# 1_Main_copy.net
KiCad netlist of a schematic drawn in Altium Designer
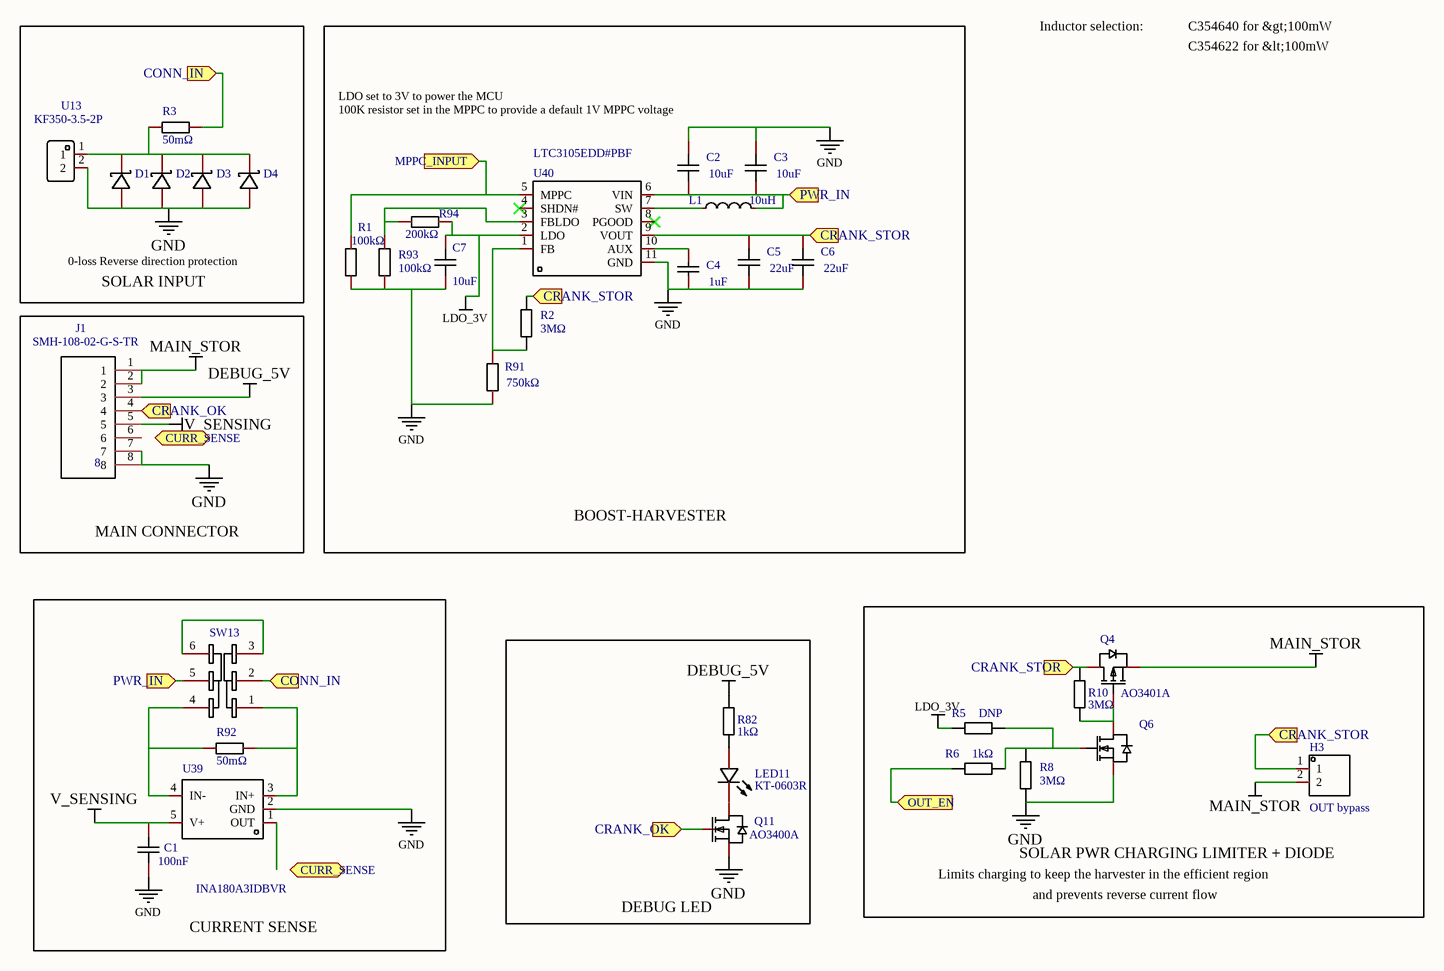
[diagram p0: 1_Main copy.schdoc]

(export (version "E")
  (design (tool "Eeschema 10.0.6"))
  (components
    (comp (ref "C1")
      (value "100nF")
      (fields
        (field (name "NAME") "100nF")
        (field (name "MANUFACTURER") "YAGEO")
        (field (name "MANUFACTURER PART") "CC0603KRX7R9BB104")
      )
      (libsource (lib "altium-import") (part "root_1_CC0603KRX7R9BB104_"))
    )
    (comp (ref "C2")
      (value "10uF")
      (fields
        (field (name "MANUFACTURER") "SAMSUNG(三星)")
        (field (name "MANUFACTURER PART") "CL10A106MA8NRNC")
        (field (name "TOLERANCE") "±20%")
      )
      (libsource (lib "altium-import") (part "root_1_CL10A106MA8NRNC_"))
    )
    (comp (ref "C3")
      (value "10uF")
      (fields
        (field (name "MANUFACTURER") "SAMSUNG(三星)")
        (field (name "MANUFACTURER PART") "CL10A106MA8NRNC")
        (field (name "TOLERANCE") "±20%")
      )
      (libsource (lib "altium-import") (part "root_1_CL10A106MA8NRNC_"))
    )
    (comp (ref "C4")
      (value "1uF")
      (fields
        (field (name "MANUFACTURER") "SAMSUNG(三星)")
        (field (name "MANUFACTURER PART") "CL10A105KB8NNNC")
        (field (name "TOLERANCE") "±10%")
      )
      (libsource (lib "altium-import") (part "root_1_CL10A105KB8NNNC_"))
    )
    (comp (ref "C5")
      (value "22uF")
      (fields
        (field (name "MANUFACTURER") "SAMSUNG(三星)")
        (field (name "MANUFACTURER PART") "CL21A226MAQNNNE")
        (field (name "TOLERANCE") "±20%")
      )
      (libsource (lib "altium-import") (part "root_1_CL21A226MAQNNNE_C45783_"))
    )
    (comp (ref "C6")
      (value "22uF")
      (fields
        (field (name "MANUFACTURER") "SAMSUNG(三星)")
        (field (name "MANUFACTURER PART") "CL21A226MAQNNNE")
        (field (name "TOLERANCE") "±20%")
      )
      (libsource (lib "altium-import") (part "root_1_CL21A226MAQNNNE_C45783_"))
    )
    (comp (ref "C7")
      (value "10uF")
      (fields
        (field (name "MANUFACTURER") "SAMSUNG(三星)")
        (field (name "MANUFACTURER PART") "CL10A106MA8NRNC")
        (field (name "TOLERANCE") "±20%")
      )
      (libsource (lib "altium-import") (part "root_1_CL10A106MA8NRNC_"))
    )
    (comp (ref "D1")
      (value "SS54")
      (description "Reverse Voltage (Vr):40V Average Rectified Current (Io):5A Forward Voltage (Vf@If):550mV@5A")
      (fields (field (name "MANUFACTURER") "MDD"))
      (libsource (lib "altium-import") (part "root_3_SS54_"))
    )
    (comp (ref "D2")
      (value "SS54")
      (description "Reverse Voltage (Vr):40V Average Rectified Current (Io):5A Forward Voltage (Vf@If):550mV@5A")
      (fields (field (name "MANUFACTURER") "MDD"))
      (libsource (lib "altium-import") (part "root_3_SS54_"))
    )
    (comp (ref "D3")
      (value "SS54")
      (description "Reverse Voltage (Vr):40V Average Rectified Current (Io):5A Forward Voltage (Vf@If):550mV@5A")
      (fields (field (name "MANUFACTURER") "MDD"))
      (libsource (lib "altium-import") (part "root_3_SS54_"))
    )
    (comp (ref "D4")
      (value "SS54")
      (description "Reverse Voltage (Vr):40V Average Rectified Current (Io):5A Forward Voltage (Vf@If):550mV@5A")
      (fields (field (name "MANUFACTURER") "MDD"))
      (libsource (lib "altium-import") (part "root_3_SS54_"))
    )
    (comp (ref "H3")
      (value "OUT bypass")
      (fields (field (name "NAME") "OUT bypass"))
      (libsource (lib "altium-import") (part "root_0_HDR-M_2.54_1x2P_"))
    )
    (comp (ref "J1")
      (value "SMH-108-02-G-S-TR")
      (fields (field (name "NAME") "SMH-108-02-G-S-TR") (field (name "NAME_1") "8"))
      (libsource (lib "altium-import") (part "root_0_SMH-108-02-G-S-TR_"))
    )
    (comp (ref "L1")
      (value "10uH")
      (fields (field (name "MANUFACTURER") "CENKER(岑科)") (field (name "MANUFACTURER PART") "CKCS6028-10uH/M"))
      (libsource (lib "altium-import") (part "root_0_CKCS6028-10uH/M_"))
    )
    (comp (ref "LED11")
      (value "KT-0603R")
      (fields (field (name "NAME") "KT-0603R") (field (name "MANUFACTURER") "KENTO"))
      (libsource (lib "altium-import") (part "root_1_KT-0603R_"))
    )
    (comp (ref "Q4")
      (value "AO3401A")
      (fields (field (name "NAME") "AO3401A") (field (name "MANUFACTURER") "AOS"))
      (libsource (lib "altium-import") (part "root_1_mirrored_AO3401A_"))
    )
    (comp (ref "Q6")
      (value "SI2302")
      (fields (field (name "MANUFACTURER") "YONGYUTAI(永裕泰)"))
      (libsource (lib "altium-import") (part "root_0_SI2302_"))
    )
    (comp (ref "Q11")
      (value "AO3400A")
      (fields (field (name "NAME") "AO3400A") (field (name "MANUFACTURER") "HUASHUO(华朔)"))
      (libsource (lib "altium-import") (part "root_0_AO3400A_"))
    )
    (comp (ref "R1")
      (value "100kΩ")
      (fields
        (field (name "MANUFACTURER") "UNI-ROYAL(厚声)")
        (field (name "MANUFACTURER PART") "0603WAF1003T5E")
        (field (name "TOLERANCE") "±1%")
      )
      (libsource (lib "altium-import") (part "root_1_0603WAF1003T5E_"))
    )
    (comp (ref "R2")
      (value "3MΩ")
      (fields
        (field (name "NAME") "3MΩ")
        (field (name "MANUFACTURER") "UniOhm")
        (field (name "MANUFACTURER PART") "0603WAF3004T5E")
      )
      (libsource (lib "altium-import") (part "root_3_0603WAF3004T5E_"))
    )
    (comp (ref "R3")
      (value "50mΩ")
      (fields
        (field (name "MANUFACTURER") "UNI-ROYAL(厚声)")
        (field (name "MANUFACTURER PART") "1206W3F500MT5E")
        (field (name "TOLERANCE") "±1%")
      )
      (libsource (lib "altium-import") (part "root_0_1206W3F500MT5E_C127691_"))
    )
    (comp (ref "R5")
      (value "DNP")
      (fields
        (field (name "NAME") "DNP")
        (field (name "MANUFACTURER") "UniOhm")
        (field (name "MANUFACTURER PART") "0603WAF1001T5E")
      )
      (libsource (lib "altium-import") (part "root_2_0603WAF1001T5E_"))
    )
    (comp (ref "R6")
      (value "1kΩ")
      (fields
        (field (name "NAME") "1kΩ")
        (field (name "MANUFACTURER") "UniOhm")
        (field (name "MANUFACTURER PART") "0603WAF1001T5E")
      )
      (libsource (lib "altium-import") (part "root_2_0603WAF1001T5E_"))
    )
    (comp (ref "R8")
      (value "3MΩ")
      (fields
        (field (name "NAME") "3MΩ")
        (field (name "MANUFACTURER") "UniOhm")
        (field (name "MANUFACTURER PART") "0603WAF3004T5E")
      )
      (libsource (lib "altium-import") (part "root_3_0603WAF3004T5E_"))
    )
    (comp (ref "R10")
      (value "3MΩ")
      (fields
        (field (name "NAME") "3MΩ")
        (field (name "MANUFACTURER") "UniOhm")
        (field (name "MANUFACTURER PART") "0603WAF3004T5E")
      )
      (libsource (lib "altium-import") (part "root_1_0603WAF3004T5E_"))
    )
    (comp (ref "R82")
      (value "1kΩ")
      (fields
        (field (name "NAME") "1kΩ")
        (field (name "MANUFACTURER") "UniOhm")
        (field (name "MANUFACTURER PART") "0603WAF1001T5E")
      )
      (libsource (lib "altium-import") (part "root_1_0603WAF1001T5E_"))
    )
    (comp (ref "R91")
      (value "750kΩ")
      (fields
        (field (name "MANUFACTURER") "UNI-ROYAL(厚声)")
        (field (name "MANUFACTURER PART") "0603WAF7503T5E")
        (field (name "TOLERANCE") "±1%")
      )
      (libsource (lib "altium-import") (part "root_1_0603WAF7503T5E_"))
    )
    (comp (ref "R92")
      (value "50mΩ")
      (fields
        (field (name "MANUFACTURER") "UNI-ROYAL(厚声)")
        (field (name "MANUFACTURER PART") "1206W3F500MT5E")
        (field (name "TOLERANCE") "±1%")
      )
      (libsource (lib "altium-import") (part "root_0_1206W3F500MT5E_C127691_"))
    )
    (comp (ref "R93")
      (value "100kΩ")
      (fields
        (field (name "MANUFACTURER") "UNI-ROYAL(厚声)")
        (field (name "MANUFACTURER PART") "0603WAF1003T5E")
        (field (name "TOLERANCE") "±1%")
      )
      (libsource (lib "altium-import") (part "root_1_0603WAF1003T5E_"))
    )
    (comp (ref "R94")
      (value "200kΩ")
      (fields
        (field (name "MANUFACTURER") "UNI-ROYAL(厚声)")
        (field (name "MANUFACTURER PART") "0603WAF2003T5E")
      )
      (libsource (lib "altium-import") (part "root_0_0603WAF2003T5E_"))
    )
    (comp (ref "SW13")
      (value "K3-2235D-F1")
      (fields (field (name "MANUFACTURER") "韩国韩荣"))
      (libsource (lib "altium-import") (part "root_1_mirrored_K3-2235D-F1_"))
    )
    (comp (ref "U13")
      (value "KF350-3.5-2P")
      (fields (field (name "NAME") "KF350-3.5-2P") (field (name "MANUFACTURER") "Cixi Kefa Elec"))
      (libsource (lib "altium-import") (part "root_2_KF350-3.5-2P_"))
    )
    (comp (ref "U39")
      (value "INA180A3IDBVR")
      (fields (field (name "LCSC PART NAME") "INA180A3IDBVR") (field (name "MANUFACTURER") "TI(德州仪器)"))
      (libsource (lib "altium-import") (part "root_2_INA180A3IDBVR_"))
    )
    (comp (ref "U40")
      (value "LTC3105EDD#PBF")
      (fields
        (field (name "MANUFACTURER") "ADI(亚德诺)/LINEAR(凌特)")
        (field (name "MANUFACTURER PART") "LTC3105EDD#PBF")
      )
      (libsource (lib "altium-import") (part "root_2_mirrored_LTC3105EDD#PBF_"))
    )
  )
  (nets
    (net (code "1") (name "/CONN_IN") (class "Default")
      (node (ref "R3") (pin "2") (pinfunction "2_2") (pintype "passive"))
      (node (ref "SW13") (pin "2") (pinfunction "2_2") (pintype "passive"))
    )
    (net (code "2") (name "/CRANK_OK") (class "Default")
      (node (ref "J1") (pin "4") (pinfunction "4_4") (pintype "passive"))
      (node (ref "Q11") (pin "1") (pinfunction "G_1") (pintype "passive"))
    )
    (net (code "3") (name "/CRANK_STOR") (class "Default")
      (node (ref "C5") (pin "2") (pinfunction "2_2") (pintype "passive"))
      (node (ref "C6") (pin "2") (pinfunction "2_2") (pintype "passive"))
      (node (ref "H3") (pin "1") (pinfunction "1_1") (pintype "passive"))
      (node (ref "Q4") (pin "3") (pinfunction "D_3") (pintype "passive"))
      (node (ref "R10") (pin "2") (pinfunction "2_2") (pintype "passive"))
      (node (ref "R2") (pin "1") (pinfunction "1_1") (pintype "passive"))
      (node (ref "U40") (pin "9") (pinfunction "VOUT_9") (pintype "passive"))
    )
    (net (code "5") (name "/MPPC_INPUT") (class "Default")
      (node (ref "R1") (pin "2") (pinfunction "2_2") (pintype "passive"))
      (node (ref "U40") (pin "5") (pinfunction "MPPC_5") (pintype "passive"))
    )
    (net (code "6") (name "/OUT_EN") (class "Default")
      (node (ref "R6") (pin "2") (pinfunction "2_2") (pintype "passive"))
    )
    (net (code "7") (name "/PWR_IN") (class "Default")
      (node (ref "C2") (pin "1") (pinfunction "1_1") (pintype "passive"))
      (node (ref "C3") (pin "1") (pinfunction "1_1") (pintype "passive"))
      (node (ref "L1") (pin "2") (pinfunction "2_2") (pintype "passive"))
      (node (ref "SW13") (pin "5") (pinfunction "5_5") (pintype "passive"))
      (node (ref "U40") (pin "6") (pinfunction "VIN_6") (pintype "passive"))
    )
    (net (code "8") (name "DEBUG_5V") (class "Default")
      (node (ref "J1") (pin "3") (pinfunction "3_3") (pintype "passive"))
      (node (ref "R82") (pin "2") (pinfunction "2_2") (pintype "passive"))
    )
    (net (code "9") (name "GND") (class "Default")
      (node (ref "C1") (pin "1") (pinfunction "1_1") (pintype "passive"))
      (node (ref "C2") (pin "2") (pinfunction "2_2") (pintype "passive"))
      (node (ref "C3") (pin "2") (pinfunction "2_2") (pintype "passive"))
      (node (ref "C4") (pin "1") (pinfunction "1_1") (pintype "passive"))
      (node (ref "C5") (pin "1") (pinfunction "1_1") (pintype "passive"))
      (node (ref "C6") (pin "1") (pinfunction "1_1") (pintype "passive"))
      (node (ref "C7") (pin "1") (pinfunction "1_1") (pintype "passive"))
      (node (ref "D1") (pin "1") (pinfunction "A_1") (pintype "passive"))
      (node (ref "D2") (pin "1") (pinfunction "A_1") (pintype "passive"))
      (node (ref "D3") (pin "1") (pinfunction "A_1") (pintype "passive"))
      (node (ref "D4") (pin "1") (pinfunction "A_1") (pintype "passive"))
      (node (ref "J1") (pin "7") (pinfunction "7_7") (pintype "passive"))
      (node (ref "J1") (pin "8") (pinfunction "8_8") (pintype "passive"))
      (node (ref "Q11") (pin "2") (pinfunction "S_2") (pintype "passive"))
      (node (ref "Q6") (pin "2") (pinfunction "S_2") (pintype "passive"))
      (node (ref "R1") (pin "1") (pinfunction "1_1") (pintype "passive"))
      (node (ref "R8") (pin "2") (pinfunction "2_2") (pintype "passive"))
      (node (ref "R91") (pin "1") (pinfunction "1_1") (pintype "passive"))
      (node (ref "R93") (pin "1") (pinfunction "1_1") (pintype "passive"))
      (node (ref "U13") (pin "2") (pinfunction "2_2") (pintype "passive"))
      (node (ref "U39") (pin "2") (pinfunction "GND_2") (pintype "passive"))
      (node (ref "U40") (pin "11") (pinfunction "GND_11") (pintype "passive"))
    )
    (net (code "10") (name "LDO_3V") (class "Default")
      (node (ref "C7") (pin "2") (pinfunction "2_2") (pintype "passive"))
      (node (ref "R5") (pin "2") (pinfunction "2_2") (pintype "passive"))
      (node (ref "R94") (pin "2") (pinfunction "2_2") (pintype "passive"))
      (node (ref "U40") (pin "2") (pinfunction "LDO_2") (pintype "passive"))
    )
    (net (code "11") (name "MAIN_STOR") (class "Default")
      (node (ref "H3") (pin "2") (pinfunction "2_2") (pintype "passive"))
      (node (ref "J1") (pin "1") (pinfunction "1_1") (pintype "passive"))
      (node (ref "J1") (pin "2") (pinfunction "2_2") (pintype "passive"))
      (node (ref "Q4") (pin "2") (pinfunction "S_2") (pintype "passive"))
    )
    (net (code "12") (name "Net-(D1-K)") (class "Default")
      (node (ref "D1") (pin "2") (pinfunction "K_2") (pintype "passive"))
      (node (ref "D2") (pin "2") (pinfunction "K_2") (pintype "passive"))
      (node (ref "D3") (pin "2") (pinfunction "K_2") (pintype "passive"))
      (node (ref "D4") (pin "2") (pinfunction "K_2") (pintype "passive"))
      (node (ref "R3") (pin "1") (pinfunction "1_1") (pintype "passive"))
      (node (ref "U13") (pin "1") (pinfunction "1_1") (pintype "passive"))
    )
    (net (code "13") (name "Net-(LED11-A)") (class "Default")
      (node (ref "LED11") (pin "1") (pinfunction "A_1") (pintype "passive"))
      (node (ref "R82") (pin "1") (pinfunction "1_1") (pintype "passive"))
    )
    (net (code "14") (name "Net-(LED11-K)") (class "Default")
      (node (ref "LED11") (pin "2") (pinfunction "K_2") (pintype "passive"))
      (node (ref "Q11") (pin "3") (pinfunction "D_3") (pintype "passive"))
    )
    (net (code "15") (name "Net-(Q4-G)") (class "Default")
      (node (ref "Q4") (pin "1") (pinfunction "G_1") (pintype "passive"))
      (node (ref "Q6") (pin "3") (pinfunction "D_3") (pintype "passive"))
      (node (ref "R10") (pin "1") (pinfunction "1_1") (pintype "passive"))
    )
    (net (code "16") (name "Net-(Q6-G)") (class "Default")
      (node (ref "Q6") (pin "1") (pinfunction "G_1") (pintype "passive"))
      (node (ref "R5") (pin "1") (pinfunction "1_1") (pintype "passive"))
      (node (ref "R6") (pin "1") (pinfunction "1_1") (pintype "passive"))
      (node (ref "R8") (pin "1") (pinfunction "1_1") (pintype "passive"))
    )
    (net (code "17") (name "Net-(SW13-Pad3)") (class "Default")
      (node (ref "SW13") (pin "3") (pinfunction "3_3") (pintype "passive"))
      (node (ref "SW13") (pin "6") (pinfunction "6_6") (pintype "passive"))
    )
    (net (code "18") (name "Net-(U39-IN+)") (class "Default")
      (node (ref "R92") (pin "2") (pinfunction "2_2") (pintype "passive"))
      (node (ref "SW13") (pin "1") (pinfunction "1_1") (pintype "passive"))
      (node (ref "U39") (pin "3") (pinfunction "IN+_3") (pintype "passive"))
    )
    (net (code "19") (name "Net-(U39-IN-)") (class "Default")
      (node (ref "R92") (pin "1") (pinfunction "1_1") (pintype "passive"))
      (node (ref "SW13") (pin "4") (pinfunction "4_4") (pintype "passive"))
      (node (ref "U39") (pin "4") (pinfunction "IN-_4") (pintype "passive"))
    )
    (net (code "20") (name "Net-(U40-AUX)") (class "Default")
      (node (ref "C4") (pin "2") (pinfunction "2_2") (pintype "passive"))
      (node (ref "U40") (pin "10") (pinfunction "AUX_10") (pintype "passive"))
    )
    (net (code "21") (name "Net-(U40-FB)") (class "Default")
      (node (ref "R2") (pin "2") (pinfunction "2_2") (pintype "passive"))
      (node (ref "R91") (pin "2") (pinfunction "2_2") (pintype "passive"))
      (node (ref "U40") (pin "1") (pinfunction "FB_1") (pintype "passive"))
    )
    (net (code "22") (name "Net-(U40-FBLDO)") (class "Default")
      (node (ref "R93") (pin "2") (pinfunction "2_2") (pintype "passive"))
      (node (ref "R94") (pin "1") (pinfunction "1_1") (pintype "passive"))
      (node (ref "U40") (pin "3") (pinfunction "FBLDO_3") (pintype "passive"))
    )
    (net (code "23") (name "Net-(U40-SW)") (class "Default")
      (node (ref "L1") (pin "1") (pinfunction "1_1") (pintype "passive"))
      (node (ref "U40") (pin "7") (pinfunction "SW_7") (pintype "passive"))
    )
    (net (code "24") (name "V_SENSING") (class "Default")
      (node (ref "C1") (pin "2") (pinfunction "2_2") (pintype "passive"))
      (node (ref "J1") (pin "5") (pinfunction "5_5") (pintype "passive"))
      (node (ref "U39") (pin "5") (pinfunction "V+_5") (pintype "passive"))
    )
    (net (code "25") (name "unconnected-(J1-Pad6)") (class "Default")
      (node (ref "J1") (pin "6") (pinfunction "6_6") (pintype "passive"))
    )
    (net (code "26") (name "unconnected-(U39-OUT-Pad1)") (class "Default")
      (node (ref "U39") (pin "1") (pinfunction "OUT_1") (pintype "passive"))
    )
    (net (code "27") (name "unconnected-(U40-PGOOD-Pad8)") (class "Default")
      (node (ref "U40") (pin "8") (pinfunction "PGOOD_8") (pintype "passive+no_connect"))
    )
    (net (code "28") (name "unconnected-(U40-SHDN#-Pad4)") (class "Default")
      (node (ref "U40") (pin "4") (pinfunction "SHDN#_4") (pintype "passive+no_connect"))
    )
  )
)
